# V2_alternatives_Layout.net
KiCad netlist of a schematic drawn in EAGLE
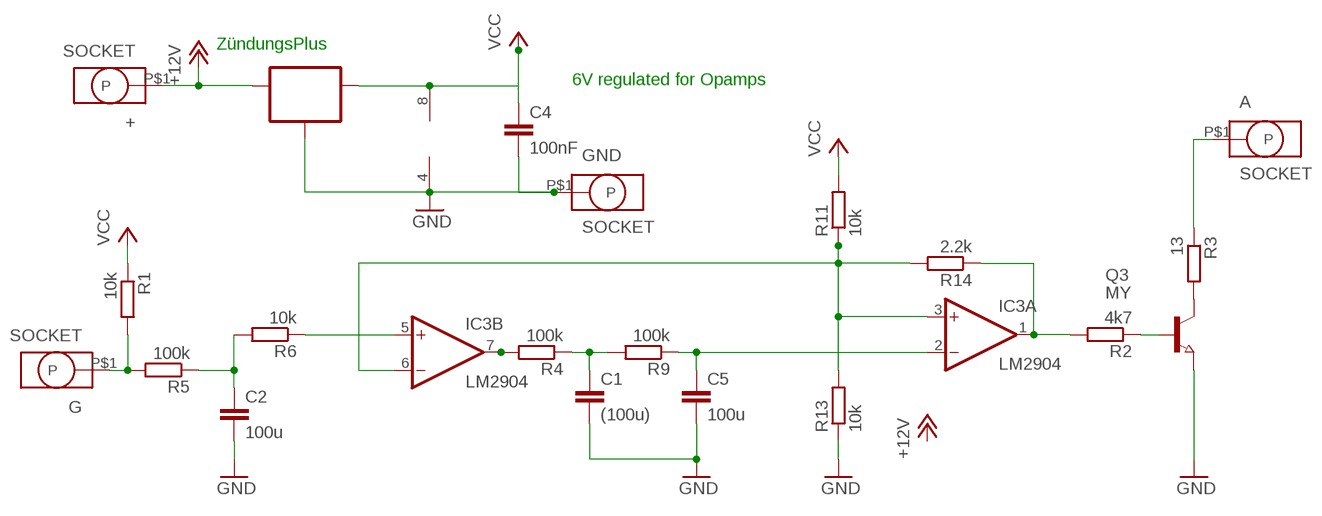
[diagram p0: schematic, sheet 1]

(export (version "E")
  (design (tool "Eeschema 10.0.6"))
  (components
    (comp (ref "+")
      (value "SOCKET")
      (footprint "eagle-import:ID2.5MM")
      (libsource (lib "eagle-import") (part "SOCKET"))
    )
    (comp (ref "A")
      (value "SOCKET")
      (footprint "eagle-import:ID2.5MM")
      (libsource (lib "eagle-import") (part "SOCKET"))
    )
    (comp (ref "C1")
      (value "(100u)")
      (footprint "eagle-import:C1206K")
      (libsource (lib "eagle-import") (part "C-EUC1206K"))
    )
    (comp (ref "C2")
      (value "100u")
      (footprint "eagle-import:C1206K")
      (libsource (lib "eagle-import") (part "C-EUC1206K"))
    )
    (comp (ref "C4")
      (value "100nF")
      (footprint "eagle-import:C0805")
      (libsource (lib "eagle-import") (part "C-EUC0805"))
    )
    (comp (ref "C5")
      (value "100u")
      (footprint "eagle-import:C1206K")
      (libsource (lib "eagle-import") (part "C-EUC1206K"))
    )
    (comp (ref "G")
      (value "SOCKET")
      (footprint "eagle-import:ID2.5MM")
      (libsource (lib "eagle-import") (part "SOCKET"))
    )
    (comp (ref "GND")
      (value "SOCKET")
      (footprint "eagle-import:ID2.5MM")
      (libsource (lib "eagle-import") (part "SOCKET"))
    )
    (comp (ref "IC2")
      (value "70L06")
      (footprint "eagle-import:SOT89_ROUND")
      (libsource (lib "eagle-import") (part "78LXXSOT89_ROUND"))
    )
    (comp (ref "IC3")
      (value "LM2904")
      (footprint "eagle-import:SO08")
      (libsource (lib "eagle-import") (part "LM358D"))
    )
    (comp (ref "Q3")
      (value "MY")
      (footprint "eagle-import:SOT89")
      (libsource (lib "eagle-import") (part "NPN-TRANSISTOR_SOT89"))
    )
    (comp (ref "R1")
      (value "10k")
      (footprint "eagle-import:R0805")
      (libsource (lib "eagle-import") (part "R-EU_R0805"))
    )
    (comp (ref "R2")
      (value "4k7")
      (footprint "eagle-import:R0805")
      (libsource (lib "eagle-import") (part "R-EU_R0805"))
    )
    (comp (ref "R3")
      (value "13")
      (footprint "eagle-import:R1206")
      (libsource (lib "eagle-import") (part "R-EU_R1206"))
    )
    (comp (ref "R4")
      (value "100k")
      (footprint "eagle-import:R0805")
      (libsource (lib "eagle-import") (part "R-EU_R0805"))
    )
    (comp (ref "R5")
      (value "100k")
      (footprint "eagle-import:R0805")
      (libsource (lib "eagle-import") (part "R-EU_R0805"))
    )
    (comp (ref "R6")
      (value "10k")
      (footprint "eagle-import:R0805")
      (libsource (lib "eagle-import") (part "R-EU_R0805"))
    )
    (comp (ref "R9")
      (value "100k")
      (footprint "eagle-import:R0805")
      (libsource (lib "eagle-import") (part "R-EU_R0805"))
    )
    (comp (ref "R11")
      (value "10k")
      (footprint "eagle-import:R0805")
      (libsource (lib "eagle-import") (part "R-EU_R0805"))
    )
    (comp (ref "R13")
      (value "10k")
      (footprint "eagle-import:R0805")
      (libsource (lib "eagle-import") (part "R-EU_R0805"))
    )
    (comp (ref "R14")
      (value "2.2k")
      (footprint "eagle-import:R0805")
      (libsource (lib "eagle-import") (part "R-EU_R0805"))
    )
  )
  (nets
    (net (code "1") (name "+12V") (class "Default")
      (node (ref "+") (pin "P$1") (pinfunction "P_P$1") (pintype "bidirectional"))
      (node (ref "IC2") (pin "3") (pinfunction "IN_3") (pintype "input"))
    )
    (net (code "2") (name "GND") (class "Default")
      (node (ref "C1") (pin "2") (pinfunction "2_2") (pintype "passive"))
      (node (ref "C2") (pin "2") (pinfunction "2_2") (pintype "passive"))
      (node (ref "C4") (pin "2") (pinfunction "2_2") (pintype "passive"))
      (node (ref "C5") (pin "2") (pinfunction "2_2") (pintype "passive"))
      (node (ref "GND") (pin "P$1") (pinfunction "P_P$1") (pintype "bidirectional"))
      (node (ref "IC2") (pin "2") (pinfunction "GND_2") (pintype "input"))
      (node (ref "IC2") (pin "2@1") (pinfunction "GND_2@1") (pintype "input"))
      (node (ref "IC3") (pin "4") (pinfunction "V-_4") (pintype "power_in"))
      (node (ref "Q3") (pin "3") (pinfunction "E_3") (pintype "passive"))
      (node (ref "R13") (pin "1") (pinfunction "1_1") (pintype "passive"))
    )
    (net (code "3") (name "Net-(A-P)") (class "Default")
      (node (ref "A") (pin "P$1") (pinfunction "P_P$1") (pintype "bidirectional"))
      (node (ref "R3") (pin "1") (pinfunction "1_1") (pintype "passive"))
    )
    (net (code "4") (name "Net-(C1-Pad1)") (class "Default")
      (node (ref "C1") (pin "1") (pinfunction "1_1") (pintype "passive"))
      (node (ref "R4") (pin "1") (pinfunction "1_1") (pintype "passive"))
      (node (ref "R9") (pin "2") (pinfunction "2_2") (pintype "passive"))
    )
    (net (code "5") (name "Net-(C2-Pad1)") (class "Default")
      (node (ref "C2") (pin "1") (pinfunction "1_1") (pintype "passive"))
      (node (ref "R5") (pin "1") (pinfunction "1_1") (pintype "passive"))
      (node (ref "R6") (pin "2") (pinfunction "2_2") (pintype "passive"))
    )
    (net (code "6") (name "Net-(G-P)") (class "Default")
      (node (ref "G") (pin "P$1") (pinfunction "P_P$1") (pintype "bidirectional"))
      (node (ref "R1") (pin "2") (pinfunction "2_2") (pintype "passive"))
      (node (ref "R5") (pin "2") (pinfunction "2_2") (pintype "passive"))
    )
    (net (code "7") (name "Net-(IC3A-+IN)") (class "Default")
      (node (ref "IC3") (pin "3") (pinfunction "+IN_3") (pintype "input"))
      (node (ref "IC3") (pin "6") (pinfunction "-IN_6") (pintype "input"))
      (node (ref "R11") (pin "1") (pinfunction "1_1") (pintype "passive"))
      (node (ref "R13") (pin "2") (pinfunction "2_2") (pintype "passive"))
      (node (ref "R14") (pin "2") (pinfunction "2_2") (pintype "passive"))
    )
    (net (code "8") (name "Net-(IC3A--IN)") (class "Default")
      (node (ref "C5") (pin "1") (pinfunction "1_1") (pintype "passive"))
      (node (ref "IC3") (pin "2") (pinfunction "-IN_2") (pintype "input"))
      (node (ref "R9") (pin "1") (pinfunction "1_1") (pintype "passive"))
    )
    (net (code "9") (name "Net-(IC3A-OUT)") (class "Default")
      (node (ref "IC3") (pin "1") (pinfunction "OUT_1") (pintype "output"))
      (node (ref "R14") (pin "1") (pinfunction "1_1") (pintype "passive"))
      (node (ref "R2") (pin "2") (pinfunction "2_2") (pintype "passive"))
    )
    (net (code "10") (name "Net-(IC3B-+IN)") (class "Default")
      (node (ref "IC3") (pin "5") (pinfunction "+IN_5") (pintype "input"))
      (node (ref "R6") (pin "1") (pinfunction "1_1") (pintype "passive"))
    )
    (net (code "11") (name "Net-(IC3B-OUT)") (class "Default")
      (node (ref "IC3") (pin "7") (pinfunction "OUT_7") (pintype "output"))
      (node (ref "R4") (pin "2") (pinfunction "2_2") (pintype "passive"))
    )
    (net (code "12") (name "Net-(Q3-B)") (class "Default")
      (node (ref "Q3") (pin "1") (pinfunction "B_1") (pintype "passive"))
      (node (ref "R2") (pin "1") (pinfunction "1_1") (pintype "passive"))
    )
    (net (code "13") (name "Net-(Q3-C)") (class "Default")
      (node (ref "Q3") (pin "2") (pinfunction "C_2") (pintype "passive"))
      (node (ref "R3") (pin "2") (pinfunction "2_2") (pintype "passive"))
    )
    (net (code "14") (name "VCC") (class "Default")
      (node (ref "C4") (pin "1") (pinfunction "1_1") (pintype "passive"))
      (node (ref "IC2") (pin "1") (pinfunction "OUT_1") (pintype "passive"))
      (node (ref "IC3") (pin "8") (pinfunction "V+_8") (pintype "power_in"))
      (node (ref "R1") (pin "1") (pinfunction "1_1") (pintype "passive"))
      (node (ref "R11") (pin "2") (pinfunction "2_2") (pintype "passive"))
    )
  )
)
